# stm32.net
KiCad netlist of a schematic drawn in Altium Designer
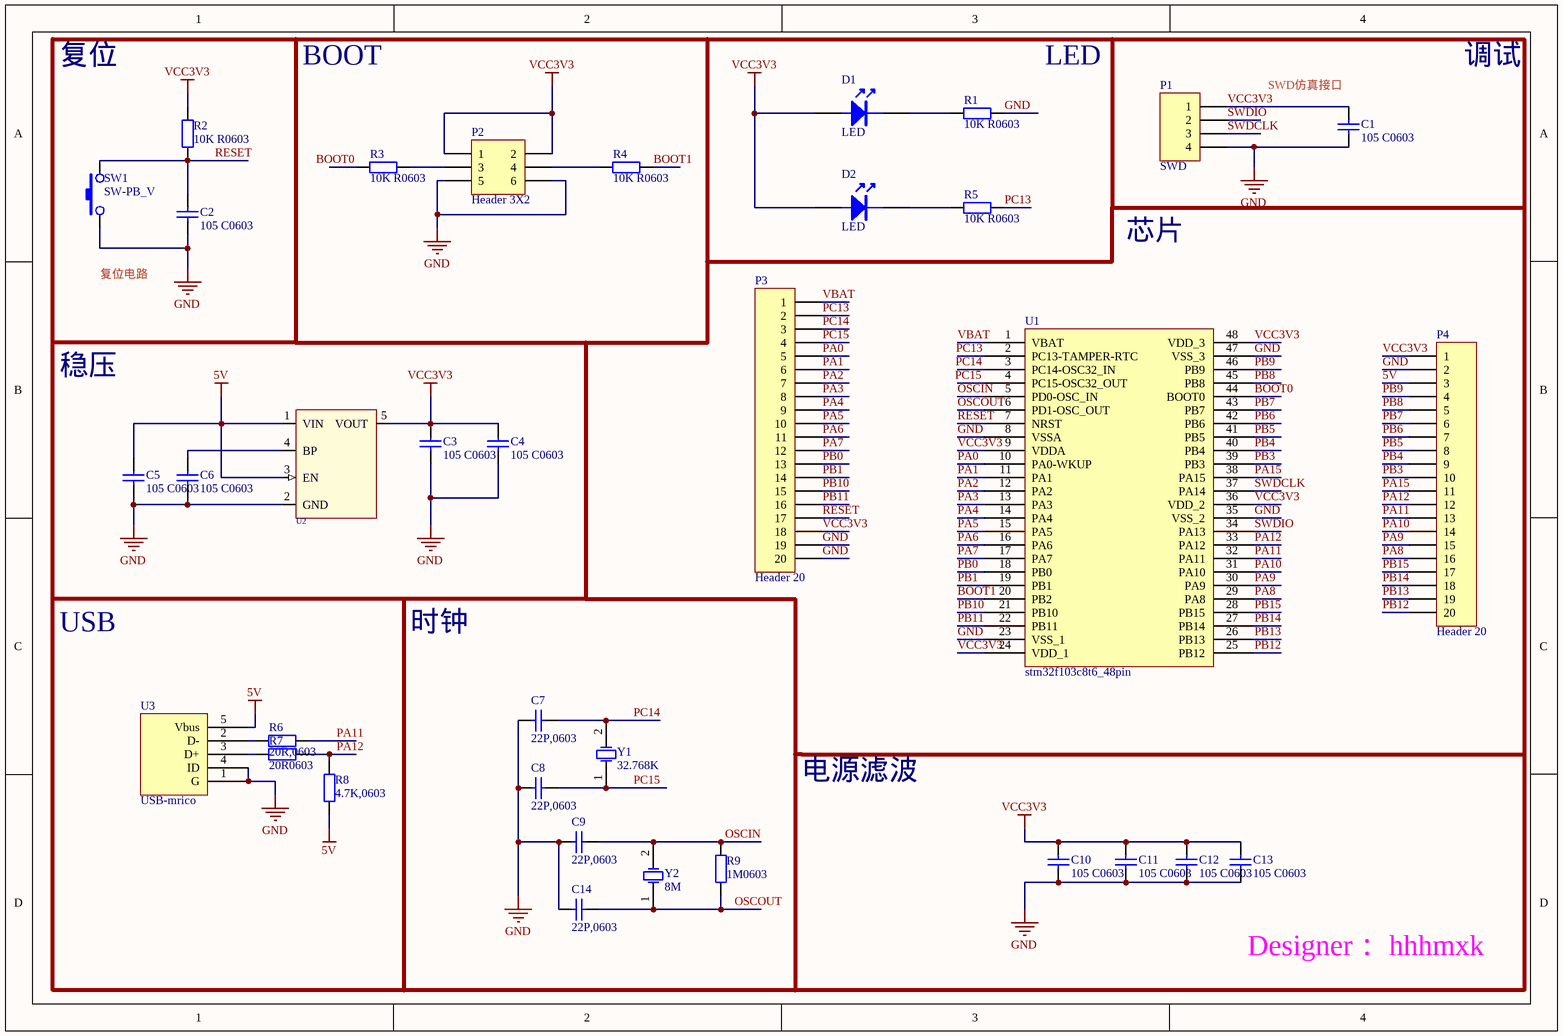
[diagram p0: stm32最小系统.SchDoc]

(export (version "E")
  (design (tool "Eeschema 10.0.6"))
  (components
    (comp (ref "C1")
      (value "105 C0603")
      (footprint "C 0603")
      (fields (field (name "PUBLISHER") "Altium Limited"))
      (libsource (lib "stm32原理图库") (part "Cap"))
    )
    (comp (ref "C2")
      (value "105 C0603")
      (footprint "C 0603")
      (fields (field (name "PUBLISHER") "Altium Limited"))
      (libsource (lib "stm32原理图库") (part "Cap"))
    )
    (comp (ref "C3")
      (value "105 C0603")
      (footprint "C 0603")
      (fields (field (name "PUBLISHER") "Altium Limited"))
      (libsource (lib "stm32原理图库") (part "Cap"))
    )
    (comp (ref "C4")
      (value "105 C0603")
      (footprint "C 0603")
      (fields (field (name "PUBLISHER") "Altium Limited"))
      (libsource (lib "stm32原理图库") (part "Cap"))
    )
    (comp (ref "C5")
      (value "105 C0603")
      (footprint "C 0603")
      (fields (field (name "PUBLISHER") "Altium Limited"))
      (libsource (lib "stm32原理图库") (part "Cap"))
    )
    (comp (ref "C6")
      (value "105 C0603")
      (footprint "C 0603")
      (fields (field (name "PUBLISHER") "Altium Limited"))
      (libsource (lib "stm32原理图库") (part "Cap"))
    )
    (comp (ref "C7")
      (value "22P,0603")
      (footprint "C 0603")
      (description "Capacitor")
      (fields (field (name "PUBLISHER") "Altium Limited"))
      (libsource (lib "STM32F103C8T6") (part "Cap"))
    )
    (comp (ref "C8")
      (value "22P,0603")
      (footprint "C 0603")
      (description "Capacitor")
      (fields (field (name "PUBLISHER") "Altium Limited"))
      (libsource (lib "STM32F103C8T6") (part "Cap"))
    )
    (comp (ref "C9")
      (value "22P,0603")
      (footprint "C 0603")
      (description "Capacitor")
      (fields (field (name "PUBLISHER") "Altium Limited"))
      (libsource (lib "STM32F103C8T6") (part "Cap"))
    )
    (comp (ref "C10")
      (value "105 C0603")
      (footprint "C 0603")
      (fields (field (name "PUBLISHER") "Altium Limited"))
      (libsource (lib "stm32原理图库") (part "Cap"))
    )
    (comp (ref "C11")
      (value "105 C0603")
      (footprint "C 0603")
      (fields (field (name "PUBLISHER") "Altium Limited"))
      (libsource (lib "stm32原理图库") (part "Cap"))
    )
    (comp (ref "C12")
      (value "105 C0603")
      (footprint "C 0603")
      (fields (field (name "PUBLISHER") "Altium Limited"))
      (libsource (lib "stm32原理图库") (part "Cap"))
    )
    (comp (ref "C13")
      (value "105 C0603")
      (footprint "C 0603")
      (fields (field (name "PUBLISHER") "Altium Limited"))
      (libsource (lib "stm32原理图库") (part "Cap"))
    )
    (comp (ref "C14")
      (value "22P,0603")
      (footprint "C 0603")
      (description "Capacitor")
      (fields (field (name "PUBLISHER") "Altium Limited"))
      (libsource (lib "STM32F103C8T6") (part "Cap"))
    )
    (comp (ref "D1") (value "LED") (footprint "LED 0805G") (libsource (lib "stm32原理图库") (part "LED")))
    (comp (ref "D2") (value "LED") (footprint "LED 0805G") (libsource (lib "stm32原理图库") (part "LED")))
    (comp (ref "P1")
      (value "SWD")
      (footprint "HDR-1X4_H")
      (description "Header, 4-Pin")
      (fields (field (name "PUBLISHER") "Altium Limited"))
      (libsource (lib "stm32原理图库") (part "Header 4"))
    )
    (comp (ref "P2")
      (value "Header 3X2")
      (footprint "HDR-3X2")
      (description "Header, 3-Pin, Dual row")
      (fields (field (name "PUBLISHER") "Altium Limited"))
      (libsource (lib "stm32原理图库") (part "Header 3X2"))
    )
    (comp (ref "P3")
      (value "Header 20")
      (footprint "HDR1X20")
      (description "Header, 20-Pin")
      (fields (field (name "PUBLISHER") "Altium Limited"))
      (libsource (lib "") (part "Header 20_1"))
    )
    (comp (ref "P4")
      (value "Header 20")
      (footprint "HDR1X20")
      (description "Header, 20-Pin")
      (fields (field (name "PUBLISHER") "Altium Limited"))
      (libsource (lib "stm32原理图库") (part "Header 20"))
    )
    (comp (ref "R1")
      (value "10K R0603")
      (footprint "R 0603")
      (fields (field (name "PUBLISHER") "Altium Limited"))
      (libsource (lib "stm32原理图库") (part "Res2"))
    )
    (comp (ref "R2")
      (value "10K R0603")
      (footprint "R 0603")
      (fields (field (name "PUBLISHER") "Altium Limited"))
      (libsource (lib "") (part "Res2_1"))
    )
    (comp (ref "R3")
      (value "10K R0603")
      (footprint "R 0603")
      (fields (field (name "PUBLISHER") "Altium Limited"))
      (libsource (lib "stm32原理图库") (part "Res2"))
    )
    (comp (ref "R4")
      (value "10K R0603")
      (footprint "R 0603")
      (fields (field (name "PUBLISHER") "Altium Limited"))
      (libsource (lib "stm32原理图库") (part "Res2"))
    )
    (comp (ref "R5")
      (value "10K R0603")
      (footprint "R 0603")
      (fields (field (name "PUBLISHER") "Altium Limited"))
      (libsource (lib "stm32原理图库") (part "Res2"))
    )
    (comp (ref "R6")
      (value "20R,0603")
      (footprint "R 0603")
      (description "Resistor")
      (fields (field (name "PUBLISHER") "Altium Limited"))
      (libsource (lib "STM32F103C8T6") (part "Res2"))
    )
    (comp (ref "R7")
      (value "20R0603")
      (footprint "R 0603")
      (description "Resistor")
      (fields (field (name "PUBLISHER") "Altium Limited"))
      (libsource (lib "STM32F103C8T6") (part "Res2"))
    )
    (comp (ref "R8")
      (value "4.7K,0603")
      (footprint "R 0603")
      (description "Resistor")
      (fields (field (name "PUBLISHER") "Altium Limited"))
      (libsource (lib "") (part "Res2_1"))
    )
    (comp (ref "R9")
      (value "1M0603")
      (footprint "R 0603")
      (description "Resistor")
      (fields (field (name "PUBLISHER") "Altium Limited"))
      (libsource (lib "") (part "Res2_1"))
    )
    (comp (ref "SW1")
      (value "SW-PB_V")
      (footprint "TSW SMD-3*6*2.5")
      (libsource (lib "stm32原理图库") (part "SW-PB_V"))
    )
    (comp (ref "U1")
      (value "stm32f103c8t6_48pin")
      (footprint "TQFP48 7x7_L")
      (libsource (lib "STM32_Schlib") (part "stm32f103c8t6_48pin"))
    )
    (comp (ref "U2")
      (value "RT9193")
      (footprint "SOT23-5L")
      (fields (field (name "ICA_PARTNUM") "$$2191094$$RT9193-15CU5") (field (name "PART NUMBER") "TMP-13"))
      (libsource (lib "stm32原理图库") (part "RT9193X_5P"))
    )
    (comp (ref "U3")
      (value "USB-mrico")
      (footprint "USB-micro_B")
      (libsource (lib "STM32F103C8T6") (part "usb-STM"))
    )
    (comp (ref "Y1")
      (value "32.768K")
      (footprint "XTAL-49S DIP")
      (description "Crystal Oscillator")
      (fields (field (name "PUBLISHER") "Altium Limited"))
      (libsource (lib "STM32F103C8T6") (part "XTAL"))
    )
    (comp (ref "Y2")
      (value "8M")
      (footprint "XTAL-49S DIP")
      (description "Crystal Oscillator")
      (fields (field (name "PUBLISHER") "Altium Limited"))
      (libsource (lib "STM32F103C8T6") (part "XTAL"))
    )
  )
  (nets
    (net (code "1") (name "/BOOT0") (class "Default")
      (node (ref "R3") (pin "1") (pinfunction "1_1") (pintype "passive"))
      (node (ref "U1") (pin "44") (pinfunction "BOOT0_44") (pintype "passive"))
    )
    (net (code "2") (name "/BOOT1") (class "Default")
      (node (ref "R4") (pin "2") (pinfunction "2_2") (pintype "passive"))
      (node (ref "U1") (pin "20") (pinfunction "PB2_20") (pintype "passive"))
    )
    (net (code "3") (name "/OSCIN") (class "Default")
      (node (ref "C9") (pin "1") (pinfunction "1_1") (pintype "passive"))
      (node (ref "R9") (pin "2") (pinfunction "2_2") (pintype "passive"))
      (node (ref "U1") (pin "5") (pinfunction "PD0-OSC_IN_5") (pintype "passive"))
      (node (ref "Y2") (pin "2") (pinfunction "OSC2_2") (pintype "passive"))
    )
    (net (code "4") (name "/OSCOUT") (class "Default")
      (node (ref "C14") (pin "1") (pinfunction "1_1") (pintype "passive"))
      (node (ref "R9") (pin "1") (pinfunction "1_1") (pintype "passive"))
      (node (ref "U1") (pin "6") (pinfunction "PD1-OSC_OUT_6") (pintype "passive"))
      (node (ref "Y2") (pin "1") (pinfunction "OSC1_1") (pintype "passive"))
    )
    (net (code "5") (name "/PA0") (class "Default")
      (node (ref "P3") (pin "5") (pinfunction "5_5") (pintype "passive"))
      (node (ref "U1") (pin "10") (pinfunction "PA0-WKUP_10") (pintype "passive"))
    )
    (net (code "6") (name "/PA1") (class "Default")
      (node (ref "P3") (pin "6") (pinfunction "6_6") (pintype "passive"))
      (node (ref "U1") (pin "11") (pinfunction "PA1_11") (pintype "passive"))
    )
    (net (code "7") (name "/PA2") (class "Default")
      (node (ref "P3") (pin "7") (pinfunction "7_7") (pintype "passive"))
      (node (ref "U1") (pin "12") (pinfunction "PA2_12") (pintype "passive"))
    )
    (net (code "8") (name "/PA3") (class "Default")
      (node (ref "P3") (pin "8") (pinfunction "8_8") (pintype "passive"))
      (node (ref "U1") (pin "13") (pinfunction "PA3_13") (pintype "passive"))
    )
    (net (code "9") (name "/PA4") (class "Default")
      (node (ref "P3") (pin "9") (pinfunction "9_9") (pintype "passive"))
      (node (ref "U1") (pin "14") (pinfunction "PA4_14") (pintype "passive"))
    )
    (net (code "10") (name "/PA5") (class "Default")
      (node (ref "P3") (pin "10") (pinfunction "10_10") (pintype "passive"))
      (node (ref "U1") (pin "15") (pinfunction "PA5_15") (pintype "passive"))
    )
    (net (code "11") (name "/PA6") (class "Default")
      (node (ref "P3") (pin "11") (pinfunction "11_11") (pintype "passive"))
      (node (ref "U1") (pin "16") (pinfunction "PA6_16") (pintype "passive"))
    )
    (net (code "12") (name "/PA7") (class "Default")
      (node (ref "P3") (pin "12") (pinfunction "12_12") (pintype "passive"))
      (node (ref "U1") (pin "17") (pinfunction "PA7_17") (pintype "passive"))
    )
    (net (code "13") (name "/PA8") (class "Default")
      (node (ref "P4") (pin "16") (pinfunction "16_16") (pintype "passive"))
      (node (ref "U1") (pin "29") (pinfunction "PA8_29") (pintype "passive"))
    )
    (net (code "14") (name "/PA9") (class "Default")
      (node (ref "P4") (pin "15") (pinfunction "15_15") (pintype "passive"))
      (node (ref "U1") (pin "30") (pinfunction "PA9_30") (pintype "passive"))
    )
    (net (code "15") (name "/PA10") (class "Default")
      (node (ref "P4") (pin "14") (pinfunction "14_14") (pintype "passive"))
      (node (ref "U1") (pin "31") (pinfunction "PA10_31") (pintype "passive"))
    )
    (net (code "16") (name "/PA11") (class "Default")
      (node (ref "P4") (pin "13") (pinfunction "13_13") (pintype "passive"))
      (node (ref "R6") (pin "2") (pinfunction "2_2") (pintype "passive"))
      (node (ref "U1") (pin "32") (pinfunction "PA11_32") (pintype "passive"))
    )
    (net (code "17") (name "/PA12") (class "Default")
      (node (ref "P4") (pin "12") (pinfunction "12_12") (pintype "passive"))
      (node (ref "R7") (pin "2") (pinfunction "2_2") (pintype "passive"))
      (node (ref "R8") (pin "2") (pinfunction "2_2") (pintype "passive"))
      (node (ref "U1") (pin "33") (pinfunction "PA12_33") (pintype "passive"))
    )
    (net (code "18") (name "/PA15") (class "Default")
      (node (ref "P4") (pin "11") (pinfunction "11_11") (pintype "passive"))
      (node (ref "U1") (pin "38") (pinfunction "PA15_38") (pintype "passive"))
    )
    (net (code "19") (name "/PB0") (class "Default")
      (node (ref "P3") (pin "13") (pinfunction "13_13") (pintype "passive"))
      (node (ref "U1") (pin "18") (pinfunction "PB0_18") (pintype "passive"))
    )
    (net (code "20") (name "/PB1") (class "Default")
      (node (ref "P3") (pin "14") (pinfunction "14_14") (pintype "passive"))
      (node (ref "U1") (pin "19") (pinfunction "PB1_19") (pintype "passive"))
    )
    (net (code "21") (name "/PB3") (class "Default")
      (node (ref "P4") (pin "10") (pinfunction "10_10") (pintype "passive"))
      (node (ref "U1") (pin "39") (pinfunction "PB3_39") (pintype "passive"))
    )
    (net (code "22") (name "/PB4") (class "Default")
      (node (ref "P4") (pin "9") (pinfunction "9_9") (pintype "passive"))
      (node (ref "U1") (pin "40") (pinfunction "PB4_40") (pintype "passive"))
    )
    (net (code "23") (name "/PB5") (class "Default")
      (node (ref "P4") (pin "8") (pinfunction "8_8") (pintype "passive"))
      (node (ref "U1") (pin "41") (pinfunction "PB5_41") (pintype "passive"))
    )
    (net (code "24") (name "/PB6") (class "Default")
      (node (ref "P4") (pin "7") (pinfunction "7_7") (pintype "passive"))
      (node (ref "U1") (pin "42") (pinfunction "PB6_42") (pintype "passive"))
    )
    (net (code "25") (name "/PB7") (class "Default")
      (node (ref "P4") (pin "6") (pinfunction "6_6") (pintype "passive"))
      (node (ref "U1") (pin "43") (pinfunction "PB7_43") (pintype "passive"))
    )
    (net (code "26") (name "/PB8") (class "Default")
      (node (ref "P4") (pin "5") (pinfunction "5_5") (pintype "passive"))
      (node (ref "U1") (pin "45") (pinfunction "PB8_45") (pintype "passive"))
    )
    (net (code "27") (name "/PB9") (class "Default")
      (node (ref "P4") (pin "4") (pinfunction "4_4") (pintype "passive"))
      (node (ref "U1") (pin "46") (pinfunction "PB9_46") (pintype "passive"))
    )
    (net (code "28") (name "/PB10") (class "Default")
      (node (ref "P3") (pin "15") (pinfunction "15_15") (pintype "passive"))
      (node (ref "U1") (pin "21") (pinfunction "PB10_21") (pintype "passive"))
    )
    (net (code "29") (name "/PB11") (class "Default")
      (node (ref "P3") (pin "16") (pinfunction "16_16") (pintype "passive"))
      (node (ref "U1") (pin "22") (pinfunction "PB11_22") (pintype "passive"))
    )
    (net (code "30") (name "/PB12") (class "Default")
      (node (ref "P4") (pin "20") (pinfunction "20_20") (pintype "passive"))
      (node (ref "U1") (pin "25") (pinfunction "PB12_25") (pintype "passive"))
    )
    (net (code "31") (name "/PB13") (class "Default")
      (node (ref "P4") (pin "19") (pinfunction "19_19") (pintype "passive"))
      (node (ref "U1") (pin "26") (pinfunction "PB13_26") (pintype "passive"))
    )
    (net (code "32") (name "/PB14") (class "Default")
      (node (ref "P4") (pin "18") (pinfunction "18_18") (pintype "passive"))
      (node (ref "U1") (pin "27") (pinfunction "PB14_27") (pintype "passive"))
    )
    (net (code "33") (name "/PB15") (class "Default")
      (node (ref "P4") (pin "17") (pinfunction "17_17") (pintype "passive"))
      (node (ref "U1") (pin "28") (pinfunction "PB15_28") (pintype "passive"))
    )
    (net (code "34") (name "/PC13") (class "Default")
      (node (ref "P3") (pin "2") (pinfunction "2_2") (pintype "passive"))
      (node (ref "R5") (pin "2") (pinfunction "2_2") (pintype "passive"))
      (node (ref "U1") (pin "2") (pinfunction "PC13-TAMPER-RTC_2") (pintype "passive"))
    )
    (net (code "35") (name "/PC14") (class "Default")
      (node (ref "C7") (pin "1") (pinfunction "1_1") (pintype "passive"))
      (node (ref "P3") (pin "3") (pinfunction "3_3") (pintype "passive"))
      (node (ref "U1") (pin "3") (pinfunction "PC14-OSC32_IN_3") (pintype "passive"))
      (node (ref "Y1") (pin "2") (pinfunction "OSC2_2") (pintype "passive"))
    )
    (net (code "36") (name "/PC15") (class "Default")
      (node (ref "C8") (pin "1") (pinfunction "1_1") (pintype "passive"))
      (node (ref "P3") (pin "4") (pinfunction "4_4") (pintype "passive"))
      (node (ref "U1") (pin "4") (pinfunction "PC15-OSC32_OUT_4") (pintype "passive"))
      (node (ref "Y1") (pin "1") (pinfunction "OSC1_1") (pintype "passive"))
    )
    (net (code "37") (name "/RESET") (class "Default")
      (node (ref "C2") (pin "2") (pinfunction "2_2") (pintype "passive"))
      (node (ref "P3") (pin "17") (pinfunction "17_17") (pintype "passive"))
      (node (ref "R2") (pin "1") (pinfunction "1_1") (pintype "passive"))
      (node (ref "SW1") (pin "2") (pinfunction "2_2") (pintype "passive"))
      (node (ref "U1") (pin "7") (pinfunction "NRST_7") (pintype "passive"))
    )
    (net (code "38") (name "/SWDCLK") (class "Default")
      (node (ref "P1") (pin "3") (pinfunction "3_3") (pintype "passive"))
      (node (ref "U1") (pin "37") (pinfunction "PA14_37") (pintype "passive"))
    )
    (net (code "39") (name "/SWDIO") (class "Default")
      (node (ref "P1") (pin "2") (pinfunction "2_2") (pintype "passive"))
      (node (ref "U1") (pin "34") (pinfunction "PA13_34") (pintype "passive"))
    )
    (net (code "40") (name "/VBAT") (class "Default")
      (node (ref "P3") (pin "1") (pinfunction "1_1") (pintype "passive"))
      (node (ref "U1") (pin "1") (pinfunction "VBAT_1") (pintype "passive"))
    )
    (net (code "41") (name "5V") (class "Default")
      (node (ref "C5") (pin "2") (pinfunction "2_2") (pintype "passive"))
      (node (ref "P4") (pin "3") (pinfunction "3_3") (pintype "passive"))
      (node (ref "R8") (pin "1") (pinfunction "1_1") (pintype "passive"))
      (node (ref "U2") (pin "1") (pinfunction "VIN_1") (pintype "power_in"))
      (node (ref "U2") (pin "3") (pinfunction "EN_3") (pintype "input"))
      (node (ref "U3") (pin "5") (pinfunction "Vbus_5") (pintype "passive"))
    )
    (net (code "42") (name "GND") (class "Default")
      (node (ref "C1") (pin "1") (pinfunction "1_1") (pintype "passive"))
      (node (ref "C10") (pin "1") (pinfunction "1_1") (pintype "passive"))
      (node (ref "C11") (pin "1") (pinfunction "1_1") (pintype "passive"))
      (node (ref "C12") (pin "1") (pinfunction "1_1") (pintype "passive"))
      (node (ref "C13") (pin "1") (pinfunction "1_1") (pintype "passive"))
      (node (ref "C14") (pin "2") (pinfunction "2_2") (pintype "passive"))
      (node (ref "C2") (pin "1") (pinfunction "1_1") (pintype "passive"))
      (node (ref "C3") (pin "1") (pinfunction "1_1") (pintype "passive"))
      (node (ref "C4") (pin "1") (pinfunction "1_1") (pintype "passive"))
      (node (ref "C5") (pin "1") (pinfunction "1_1") (pintype "passive"))
      (node (ref "C6") (pin "1") (pinfunction "1_1") (pintype "passive"))
      (node (ref "C7") (pin "2") (pinfunction "2_2") (pintype "passive"))
      (node (ref "C8") (pin "2") (pinfunction "2_2") (pintype "passive"))
      (node (ref "C9") (pin "2") (pinfunction "2_2") (pintype "passive"))
      (node (ref "P1") (pin "4") (pinfunction "4_4") (pintype "passive"))
      (node (ref "P2") (pin "5") (pinfunction "5_5") (pintype "passive"))
      (node (ref "P2") (pin "6") (pinfunction "6_6") (pintype "passive"))
      (node (ref "P3") (pin "19") (pinfunction "19_19") (pintype "passive"))
      (node (ref "P3") (pin "20") (pinfunction "20_20") (pintype "passive"))
      (node (ref "P4") (pin "2") (pinfunction "2_2") (pintype "passive"))
      (node (ref "R1") (pin "2") (pinfunction "2_2") (pintype "passive"))
      (node (ref "SW1") (pin "1") (pinfunction "1_1") (pintype "passive"))
      (node (ref "U1") (pin "23") (pinfunction "VSS_1_23") (pintype "passive"))
      (node (ref "U1") (pin "35") (pinfunction "VSS_2_35") (pintype "passive"))
      (node (ref "U1") (pin "47") (pinfunction "VSS_3_47") (pintype "passive"))
      (node (ref "U1") (pin "8") (pinfunction "VSSA_8") (pintype "passive"))
      (node (ref "U2") (pin "2") (pinfunction "GND_2") (pintype "power_in"))
      (node (ref "U3") (pin "1") (pinfunction "G_1") (pintype "passive"))
      (node (ref "U3") (pin "4") (pinfunction "ID_4") (pintype "passive"))
    )
    (net (code "43") (name "Net-(D1-Pad2)") (class "Default")
      (node (ref "D1") (pin "2") (pinfunction "2_2") (pintype "passive"))
      (node (ref "R1") (pin "1") (pinfunction "1_1") (pintype "passive"))
    )
    (net (code "44") (name "Net-(D2-Pad2)") (class "Default")
      (node (ref "D2") (pin "2") (pinfunction "2_2") (pintype "passive"))
      (node (ref "R5") (pin "1") (pinfunction "1_1") (pintype "passive"))
    )
    (net (code "45") (name "Net-(P2-Pad3)") (class "Default")
      (node (ref "P2") (pin "3") (pinfunction "3_3") (pintype "passive"))
      (node (ref "R3") (pin "2") (pinfunction "2_2") (pintype "passive"))
    )
    (net (code "46") (name "Net-(P2-Pad4)") (class "Default")
      (node (ref "P2") (pin "4") (pinfunction "4_4") (pintype "passive"))
      (node (ref "R4") (pin "1") (pinfunction "1_1") (pintype "passive"))
    )
    (net (code "47") (name "Net-(U2-BP)") (class "Default")
      (node (ref "C6") (pin "2") (pinfunction "2_2") (pintype "passive"))
      (node (ref "U2") (pin "4") (pinfunction "BP_4") (pintype "passive"))
    )
    (net (code "48") (name "Net-(U3-D+)") (class "Default")
      (node (ref "R7") (pin "1") (pinfunction "1_1") (pintype "passive"))
      (node (ref "U3") (pin "3") (pinfunction "D+_3") (pintype "passive"))
    )
    (net (code "49") (name "Net-(U3-D-)") (class "Default")
      (node (ref "R6") (pin "1") (pinfunction "1_1") (pintype "passive"))
      (node (ref "U3") (pin "2") (pinfunction "D-_2") (pintype "passive"))
    )
    (net (code "50") (name "VCC3V3") (class "Default")
      (node (ref "C1") (pin "2") (pinfunction "2_2") (pintype "passive"))
      (node (ref "C10") (pin "2") (pinfunction "2_2") (pintype "passive"))
      (node (ref "C11") (pin "2") (pinfunction "2_2") (pintype "passive"))
      (node (ref "C12") (pin "2") (pinfunction "2_2") (pintype "passive"))
      (node (ref "C13") (pin "2") (pinfunction "2_2") (pintype "passive"))
      (node (ref "C3") (pin "2") (pinfunction "2_2") (pintype "passive"))
      (node (ref "C4") (pin "2") (pinfunction "2_2") (pintype "passive"))
      (node (ref "D1") (pin "1") (pinfunction "1_1") (pintype "passive"))
      (node (ref "D2") (pin "1") (pinfunction "1_1") (pintype "passive"))
      (node (ref "P1") (pin "1") (pinfunction "1_1") (pintype "passive"))
      (node (ref "P2") (pin "1") (pinfunction "1_1") (pintype "passive"))
      (node (ref "P2") (pin "2") (pinfunction "2_2") (pintype "passive"))
      (node (ref "P3") (pin "18") (pinfunction "18_18") (pintype "passive"))
      (node (ref "P4") (pin "1") (pinfunction "1_1") (pintype "passive"))
      (node (ref "R2") (pin "2") (pinfunction "2_2") (pintype "passive"))
      (node (ref "U1") (pin "24") (pinfunction "VDD_1_24") (pintype "passive"))
      (node (ref "U1") (pin "36") (pinfunction "VDD_2_36") (pintype "passive"))
      (node (ref "U1") (pin "48") (pinfunction "VDD_3_48") (pintype "passive"))
      (node (ref "U1") (pin "9") (pinfunction "VDDA_9") (pintype "passive"))
      (node (ref "U2") (pin "5") (pinfunction "VOUT_5") (pintype "power_in"))
    )
  )
)
